# GMSN_Pure_Power.net
KiCad netlist of a schematic drawn in EAGLE
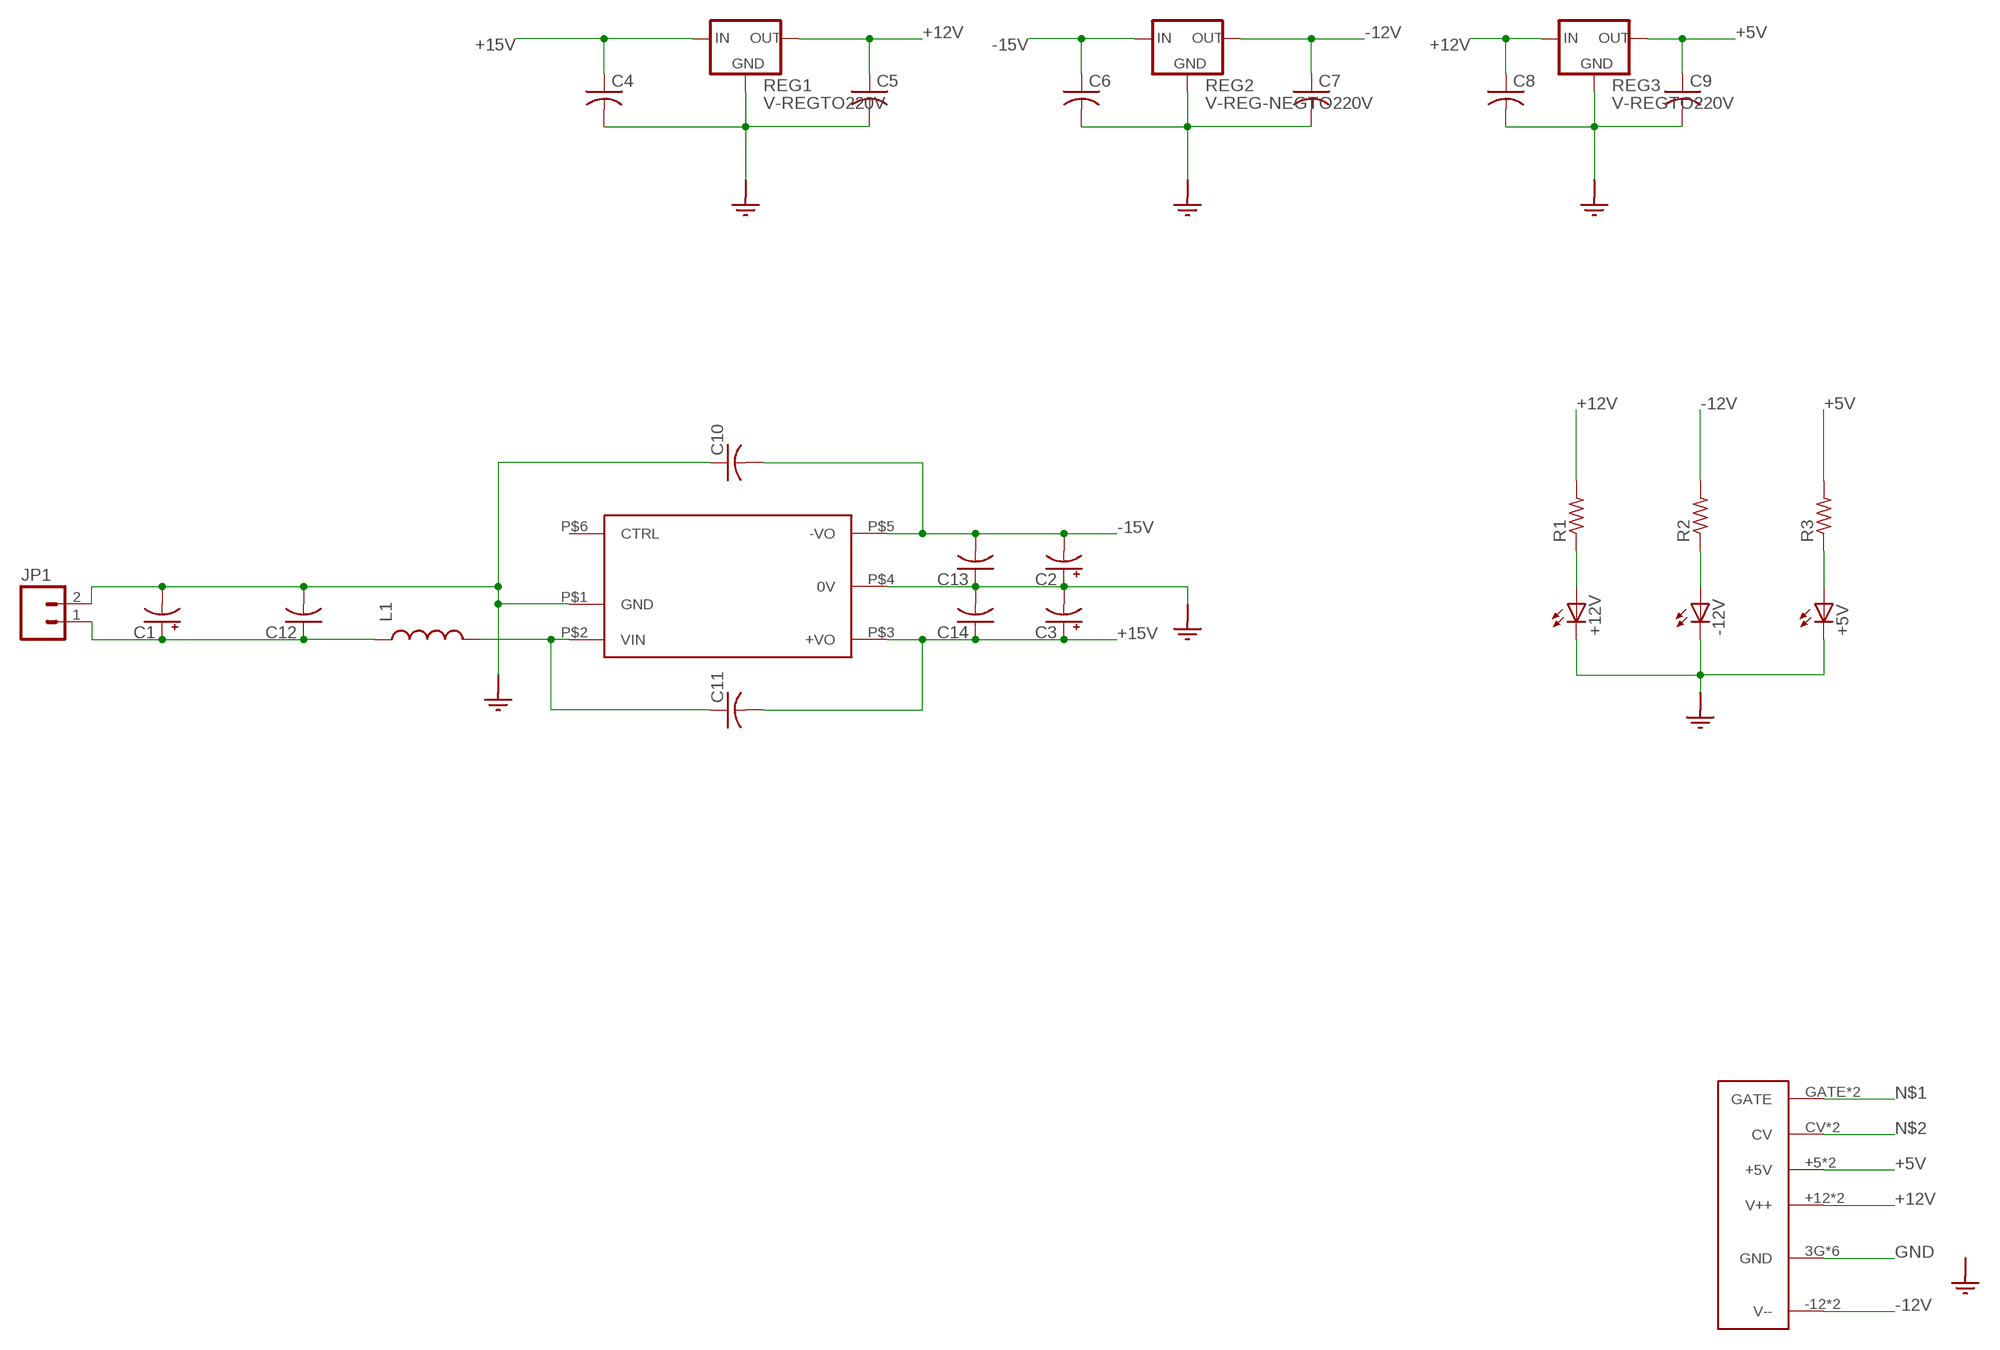
[diagram p0: schematic, sheet 1]

(export (version "E")
  (design (tool "Eeschema 10.0.6"))
  (components
    (comp (ref "+5V")
      (value "LED5MM")
      (footprint "eagle-import:LED5MM")
      (libsource (lib "eagle-import") (part "LED5MM"))
    )
    (comp (ref "+12V")
      (value "LED5MM")
      (footprint "eagle-import:LED5MM")
      (libsource (lib "eagle-import") (part "LED5MM"))
    )
    (comp (ref "-12V")
      (value "LED5MM")
      (footprint "eagle-import:LED5MM")
      (libsource (lib "eagle-import") (part "LED5MM"))
    )
    (comp (ref "C1")
      (value "CPOL-USSANYO_D")
      (footprint "eagle-import:SANYO-OSCON_D")
      (libsource (lib "eagle-import") (part "CPOL-USSANYO_D"))
    )
    (comp (ref "C2")
      (value "CPOL-USSANYO_D")
      (footprint "eagle-import:SANYO-OSCON_D")
      (libsource (lib "eagle-import") (part "CPOL-USSANYO_D"))
    )
    (comp (ref "C3")
      (value "CPOL-USSANYO_D")
      (footprint "eagle-import:SANYO-OSCON_D")
      (libsource (lib "eagle-import") (part "CPOL-USSANYO_D"))
    )
    (comp (ref "C4")
      (value "C-US025-024X044")
      (footprint "eagle-import:C025-024X044")
      (libsource (lib "eagle-import") (part "C-US025-024X044"))
    )
    (comp (ref "C5")
      (value "C-US025-024X044")
      (footprint "eagle-import:C025-024X044")
      (libsource (lib "eagle-import") (part "C-US025-024X044"))
    )
    (comp (ref "C6")
      (value "C-US025-024X044")
      (footprint "eagle-import:C025-024X044")
      (libsource (lib "eagle-import") (part "C-US025-024X044"))
    )
    (comp (ref "C7")
      (value "C-US025-024X044")
      (footprint "eagle-import:C025-024X044")
      (libsource (lib "eagle-import") (part "C-US025-024X044"))
    )
    (comp (ref "C8")
      (value "C-US025-024X044")
      (footprint "eagle-import:C025-024X044")
      (libsource (lib "eagle-import") (part "C-US025-024X044"))
    )
    (comp (ref "C9")
      (value "C-US025-024X044")
      (footprint "eagle-import:C025-024X044")
      (libsource (lib "eagle-import") (part "C-US025-024X044"))
    )
    (comp (ref "C10")
      (value "C-US025-024X044")
      (footprint "eagle-import:C025-024X044")
      (libsource (lib "eagle-import") (part "C-US025-024X044"))
    )
    (comp (ref "C11")
      (value "C-US025-024X044")
      (footprint "eagle-import:C025-024X044")
      (libsource (lib "eagle-import") (part "C-US025-024X044"))
    )
    (comp (ref "C12")
      (value "C-US025-024X044")
      (footprint "eagle-import:C025-024X044")
      (libsource (lib "eagle-import") (part "C-US025-024X044"))
    )
    (comp (ref "C13")
      (value "C-US025-024X044")
      (footprint "eagle-import:C025-024X044")
      (libsource (lib "eagle-import") (part "C-US025-024X044"))
    )
    (comp (ref "C14")
      (value "C-US025-024X044")
      (footprint "eagle-import:C025-024X044")
      (libsource (lib "eagle-import") (part "C-US025-024X044"))
    )
    (comp (ref "JP1")
      (value "M02LOCK")
      (footprint "eagle-import:1X02_LOCK")
      (libsource (lib "eagle-import") (part "M02LOCK"))
    )
    (comp (ref "L1")
      (value "INDUCTORAXIAL-0.6")
      (footprint "eagle-import:AXIAL-0.6")
      (libsource (lib "eagle-import") (part "INDUCTORAXIAL-0.6"))
    )
    (comp (ref "R1")
      (value "R-US_0207/10")
      (footprint "eagle-import:0207_10")
      (libsource (lib "eagle-import") (part "R-US_0207/10"))
    )
    (comp (ref "R2")
      (value "R-US_0207/10")
      (footprint "eagle-import:0207_10")
      (libsource (lib "eagle-import") (part "R-US_0207/10"))
    )
    (comp (ref "R3")
      (value "R-US_0207/10")
      (footprint "eagle-import:0207_10")
      (libsource (lib "eagle-import") (part "R-US_0207/10"))
    )
    (comp (ref "REG1")
      (value "V-REGTO220V")
      (footprint "eagle-import:TO220V")
      (libsource (lib "eagle-import") (part "V-REGTO220V"))
    )
    (comp (ref "REG2")
      (value "V-REG-NEGTO220V")
      (footprint "eagle-import:TO220V")
      (libsource (lib "eagle-import") (part "V-REG-NEGTO220V"))
    )
    (comp (ref "REG3")
      (value "V-REGTO220V")
      (footprint "eagle-import:TO220V")
      (libsource (lib "eagle-import") (part "V-REGTO220V"))
    )
    (comp (ref "U$1")
      (value "URA241XLD-20WR3")
      (footprint "eagle-import:URA241XLD-20WR3")
      (libsource (lib "eagle-import") (part "URA241XLD-20WR3"))
    )
    (comp (ref "U$11")
      (value "EURO_POWER_16")
      (footprint "eagle-import:POWER_SHROUDED")
      (libsource (lib "eagle-import") (part "EURO_POWER_16"))
    )
  )
  (nets
    (net (code "1") (name "/+5V") (class "Default")
      (node (ref "C9") (pin "1") (pinfunction "1_1") (pintype "passive"))
      (node (ref "R3") (pin "2") (pinfunction "2_2") (pintype "passive"))
      (node (ref "REG3") (pin "3") (pinfunction "OUT_3") (pintype "passive"))
      (node (ref "U$11") (pin "+5") (pinfunction "+5V_+5") (pintype "bidirectional"))
      (node (ref "U$11") (pin "+5A") (pinfunction "+5V_+5A") (pintype "bidirectional"))
    )
    (net (code "2") (name "/+12V") (class "Default")
      (node (ref "C5") (pin "1") (pinfunction "1_1") (pintype "passive"))
      (node (ref "C8") (pin "1") (pinfunction "1_1") (pintype "passive"))
      (node (ref "R1") (pin "2") (pinfunction "2_2") (pintype "passive"))
      (node (ref "REG1") (pin "3") (pinfunction "OUT_3") (pintype "passive"))
      (node (ref "REG3") (pin "1") (pinfunction "IN_1") (pintype "input"))
      (node (ref "U$11") (pin "+12") (pinfunction "V++_+12") (pintype "bidirectional"))
      (node (ref "U$11") (pin "+12A") (pinfunction "V++_+12A") (pintype "bidirectional"))
    )
    (net (code "3") (name "/+15V") (class "Default")
      (node (ref "C11") (pin "2") (pinfunction "2_2") (pintype "passive"))
      (node (ref "C14") (pin "1") (pinfunction "1_1") (pintype "passive"))
      (node (ref "C3") (pin "+") (pinfunction "+_+") (pintype "passive"))
      (node (ref "C4") (pin "1") (pinfunction "1_1") (pintype "passive"))
      (node (ref "REG1") (pin "1") (pinfunction "IN_1") (pintype "input"))
      (node (ref "U$1") (pin "P$3") (pinfunction "+VO_P$3") (pintype "bidirectional"))
    )
    (net (code "4") (name "/-12V") (class "Default")
      (node (ref "C7") (pin "1") (pinfunction "1_1") (pintype "passive"))
      (node (ref "R2") (pin "2") (pinfunction "2_2") (pintype "passive"))
      (node (ref "REG2") (pin "3") (pinfunction "OUT_3") (pintype "passive"))
      (node (ref "U$11") (pin "-12") (pinfunction "V--_-12") (pintype "bidirectional"))
      (node (ref "U$11") (pin "-12A") (pinfunction "V--_-12A") (pintype "bidirectional"))
    )
    (net (code "5") (name "/-15V") (class "Default")
      (node (ref "C10") (pin "2") (pinfunction "2_2") (pintype "passive"))
      (node (ref "C13") (pin "2") (pinfunction "2_2") (pintype "passive"))
      (node (ref "C2") (pin "-") (pinfunction "-_-") (pintype "passive"))
      (node (ref "C6") (pin "1") (pinfunction "1_1") (pintype "passive"))
      (node (ref "REG2") (pin "2") (pinfunction "IN_2") (pintype "input"))
      (node (ref "U$1") (pin "P$5") (pinfunction "-VO_P$5") (pintype "bidirectional"))
    )
    (net (code "6") (name "/N$1") (class "Default")
      (node (ref "U$11") (pin "GATE") (pinfunction "GATE_GATE") (pintype "bidirectional"))
      (node (ref "U$11") (pin "GATEA") (pinfunction "GATE_GATEA") (pintype "bidirectional"))
    )
    (net (code "7") (name "/N$2") (class "Default")
      (node (ref "U$11") (pin "CV") (pinfunction "CV_CV") (pintype "bidirectional"))
      (node (ref "U$11") (pin "CVA") (pinfunction "CV_CVA") (pintype "bidirectional"))
    )
    (net (code "8") (name "GND") (class "Default")
      (node (ref "+12V") (pin "K") (pinfunction "C_K") (pintype "passive"))
      (node (ref "+5V") (pin "K") (pinfunction "C_K") (pintype "passive"))
      (node (ref "-12V") (pin "K") (pinfunction "C_K") (pintype "passive"))
      (node (ref "C1") (pin "-") (pinfunction "-_-") (pintype "passive"))
      (node (ref "C10") (pin "1") (pinfunction "1_1") (pintype "passive"))
      (node (ref "C12") (pin "2") (pinfunction "2_2") (pintype "passive"))
      (node (ref "C13") (pin "1") (pinfunction "1_1") (pintype "passive"))
      (node (ref "C14") (pin "2") (pinfunction "2_2") (pintype "passive"))
      (node (ref "C2") (pin "+") (pinfunction "+_+") (pintype "passive"))
      (node (ref "C3") (pin "-") (pinfunction "-_-") (pintype "passive"))
      (node (ref "C4") (pin "2") (pinfunction "2_2") (pintype "passive"))
      (node (ref "C5") (pin "2") (pinfunction "2_2") (pintype "passive"))
      (node (ref "C6") (pin "2") (pinfunction "2_2") (pintype "passive"))
      (node (ref "C7") (pin "2") (pinfunction "2_2") (pintype "passive"))
      (node (ref "C8") (pin "2") (pinfunction "2_2") (pintype "passive"))
      (node (ref "C9") (pin "2") (pinfunction "2_2") (pintype "passive"))
      (node (ref "JP1") (pin "2") (pinfunction "2_2") (pintype "passive"))
      (node (ref "REG1") (pin "2") (pinfunction "GND_2") (pintype "input"))
      (node (ref "REG2") (pin "1") (pinfunction "GND_1") (pintype "input"))
      (node (ref "REG3") (pin "2") (pinfunction "GND_2") (pintype "input"))
      (node (ref "U$1") (pin "P$1") (pinfunction "GND_P$1") (pintype "bidirectional"))
      (node (ref "U$1") (pin "P$4") (pinfunction "0V_P$4") (pintype "bidirectional"))
      (node (ref "U$11") (pin "3G") (pinfunction "GND_3G") (pintype "bidirectional"))
      (node (ref "U$11") (pin "4G") (pinfunction "GND_4G") (pintype "bidirectional"))
      (node (ref "U$11") (pin "5G") (pinfunction "GND_5G") (pintype "bidirectional"))
      (node (ref "U$11") (pin "6G") (pinfunction "GND_6G") (pintype "bidirectional"))
      (node (ref "U$11") (pin "7G") (pinfunction "GND_7G") (pintype "bidirectional"))
      (node (ref "U$11") (pin "8G") (pinfunction "GND_8G") (pintype "bidirectional"))
    )
    (net (code "9") (name "Net-(+5V-PadA)") (class "Default")
      (node (ref "+5V") (pin "A") (pinfunction "A_A") (pintype "passive"))
      (node (ref "R3") (pin "1") (pinfunction "1_1") (pintype "passive"))
    )
    (net (code "10") (name "Net-(+12V-PadA)") (class "Default")
      (node (ref "+12V") (pin "A") (pinfunction "A_A") (pintype "passive"))
      (node (ref "R1") (pin "1") (pinfunction "1_1") (pintype "passive"))
    )
    (net (code "11") (name "Net-(-12V-PadA)") (class "Default")
      (node (ref "-12V") (pin "A") (pinfunction "A_A") (pintype "passive"))
      (node (ref "R2") (pin "1") (pinfunction "1_1") (pintype "passive"))
    )
    (net (code "12") (name "Net-(L1-1)") (class "Default")
      (node (ref "C1") (pin "+") (pinfunction "+_+") (pintype "passive"))
      (node (ref "C12") (pin "1") (pinfunction "1_1") (pintype "passive"))
      (node (ref "JP1") (pin "1") (pinfunction "1_1") (pintype "passive"))
      (node (ref "L1") (pin "P$1") (pinfunction "1_P$1") (pintype "passive"))
    )
    (net (code "13") (name "Net-(L1-2)") (class "Default")
      (node (ref "C11") (pin "1") (pinfunction "1_1") (pintype "passive"))
      (node (ref "L1") (pin "P$2") (pinfunction "2_P$2") (pintype "passive"))
      (node (ref "U$1") (pin "P$2") (pinfunction "VIN_P$2") (pintype "bidirectional"))
    )
    (net (code "14") (name "unconnected-(U$1-CTRL-PadP$6)") (class "Default")
      (node (ref "U$1") (pin "P$6") (pinfunction "CTRL_P$6") (pintype "bidirectional"))
    )
  )
)
